# board.net
KiCad netlist of a schematic drawn in EAGLE
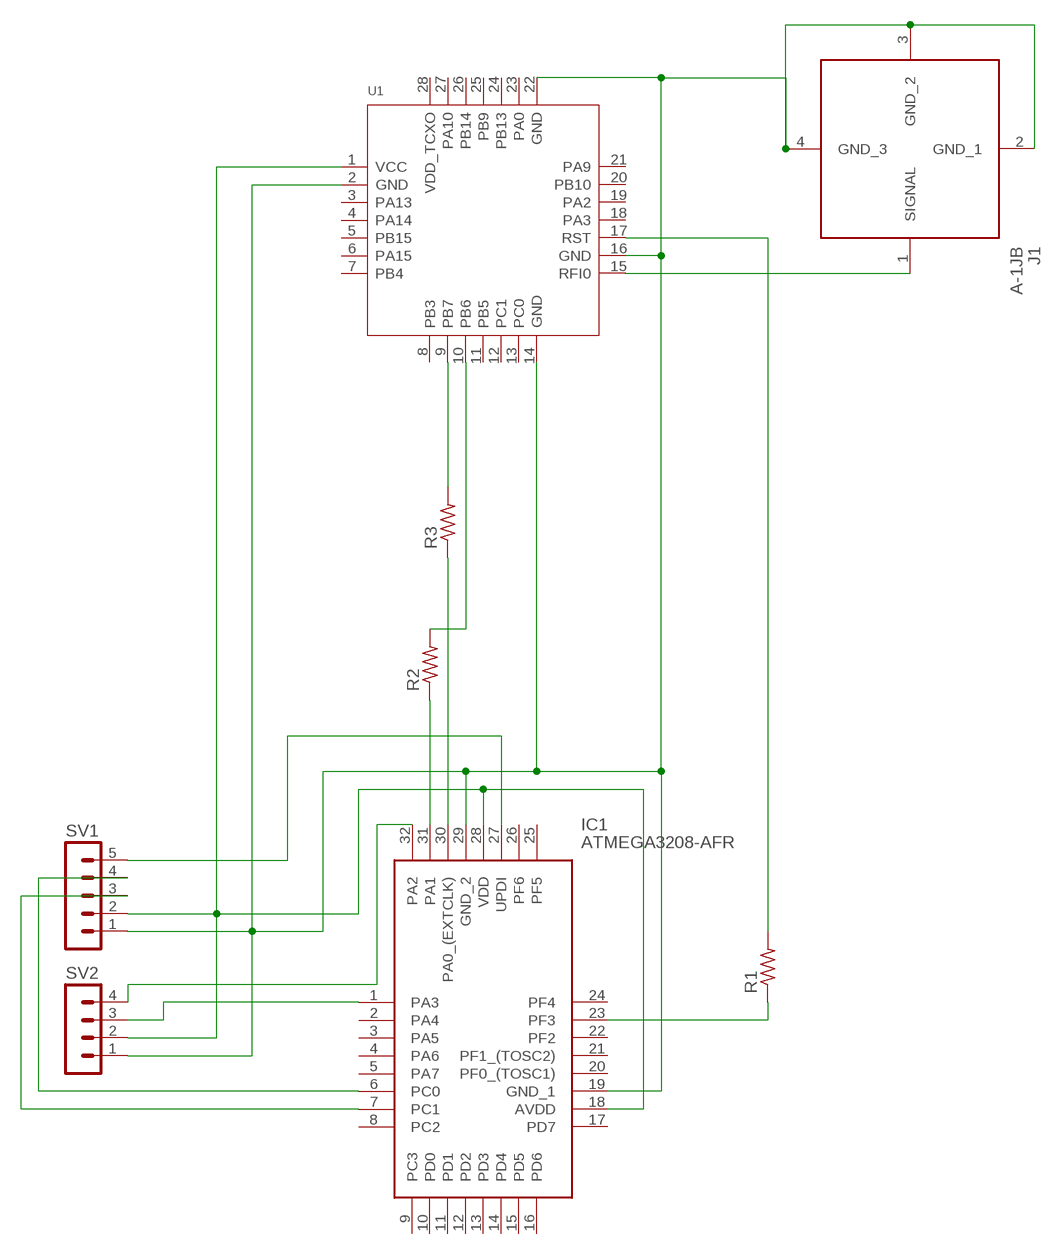
[diagram p0: schematic, sheet 1]

(export (version "E")
  (design (tool "Eeschema 10.0.6"))
  (components
    (comp (ref "IC1")
      (value "ATMEGA3208-AFR")
      (footprint "eagle-import:QFP80P900X900X120-32N")
      (fields (field (name "MOUSER_PART_NUMBER") "579-ATMEGA3208AFR"))
      (libsource (lib "eagle-import") (part "ATMEGA3208-AFR"))
    )
    (comp (ref "J1")
      (value "A-1JB")
      (footprint "eagle-import:A1JB")
      (fields (field (name "MOUSER_PART_NUMBER") "523-A-1JB"))
      (libsource (lib "eagle-import") (part "A-1JB"))
    )
    (comp (ref "R1")
      (value "22")
      (footprint "eagle-import:RES_0805")
      (fields
        (field (name "DIGIKEY_PART_NUMBER") "541-0.0ATR-ND")
        (field (name "MANUFACTURER") "Vishay Dale")
        (field (name "MPN") "CRCW08050000Z0EA")
        (field (name "CREATED_BY") "PCBLayout.com")
      )
      (libsource (lib "eagle-import") (part "CRCW08050000Z0EA"))
    )
    (comp (ref "R2")
      (value "22")
      (footprint "eagle-import:RES_0805")
      (fields
        (field (name "DIGIKEY_PART_NUMBER") "541-0.0ATR-ND")
        (field (name "MANUFACTURER") "Vishay Dale")
        (field (name "MPN") "CRCW08050000Z0EA")
        (field (name "CREATED_BY") "PCBLayout.com")
      )
      (libsource (lib "eagle-import") (part "CRCW08050000Z0EA"))
    )
    (comp (ref "R3")
      (value "22")
      (footprint "eagle-import:RES_0805")
      (fields
        (field (name "DIGIKEY_PART_NUMBER") "541-0.0ATR-ND")
        (field (name "MANUFACTURER") "Vishay Dale")
        (field (name "MPN") "CRCW08050000Z0EA")
        (field (name "CREATED_BY") "PCBLayout.com")
      )
      (libsource (lib "eagle-import") (part "CRCW08050000Z0EA"))
    )
    (comp (ref "SV1")
      (value "MA05-1")
      (footprint "eagle-import:MA05-1")
      (libsource (lib "eagle-import") (part "MA05-1"))
    )
    (comp (ref "SV2")
      (value "MA04-1")
      (footprint "eagle-import:MA04-1")
      (libsource (lib "eagle-import") (part "MA04-1"))
    )
    (comp (ref "U1")
      (value "MODULE_LORA_E5")
      (footprint "eagle-import:MODULE28P-1.25-12X12X2.5MM")
      (libsource (lib "eagle-import") (part "MODULE_LORA_E5"))
    )
  )
  (nets
    (net (code "1") (name "Net-(IC1-AVDD)") (class "Default")
      (node (ref "IC1") (pin "18") (pinfunction "AVDD_18") (pintype "bidirectional"))
      (node (ref "IC1") (pin "28") (pinfunction "VDD_28") (pintype "bidirectional"))
      (node (ref "SV1") (pin "2") (pinfunction "2_2") (pintype "passive"))
      (node (ref "SV2") (pin "2") (pinfunction "2_2") (pintype "passive"))
      (node (ref "U1") (pin "1") (pinfunction "VCC_1") (pintype "bidirectional"))
    )
    (net (code "2") (name "Net-(IC1-GND_1)") (class "Default")
      (node (ref "IC1") (pin "19") (pinfunction "GND_1_19") (pintype "bidirectional"))
      (node (ref "IC1") (pin "29") (pinfunction "GND_2_29") (pintype "bidirectional"))
      (node (ref "J1") (pin "2") (pinfunction "GND_1_2") (pintype "bidirectional"))
      (node (ref "J1") (pin "3") (pinfunction "GND_2_3") (pintype "bidirectional"))
      (node (ref "J1") (pin "4") (pinfunction "GND_3_4") (pintype "bidirectional"))
      (node (ref "SV1") (pin "1") (pinfunction "1_1") (pintype "passive"))
      (node (ref "SV2") (pin "1") (pinfunction "1_1") (pintype "passive"))
      (node (ref "U1") (pin "14") (pinfunction "GND_14") (pintype "bidirectional"))
      (node (ref "U1") (pin "16") (pinfunction "GND_16") (pintype "bidirectional"))
      (node (ref "U1") (pin "2") (pinfunction "GND_2") (pintype "bidirectional"))
      (node (ref "U1") (pin "22") (pinfunction "GND_22") (pintype "bidirectional"))
    )
    (net (code "3") (name "Net-(IC1-PA0_(EXTCLK))") (class "Default")
      (node (ref "IC1") (pin "30") (pinfunction "PA0_(EXTCLK)_30") (pintype "bidirectional"))
      (node (ref "R3") (pin "1") (pinfunction "1_1") (pintype "passive"))
    )
    (net (code "4") (name "Net-(IC1-PA1)") (class "Default")
      (node (ref "IC1") (pin "31") (pinfunction "PA1_31") (pintype "bidirectional"))
      (node (ref "R2") (pin "1") (pinfunction "1_1") (pintype "passive"))
    )
    (net (code "5") (name "Net-(IC1-PA2)") (class "Default")
      (node (ref "IC1") (pin "32") (pinfunction "PA2_32") (pintype "bidirectional"))
      (node (ref "SV2") (pin "4") (pinfunction "4_4") (pintype "passive"))
    )
    (net (code "6") (name "Net-(IC1-PA3)") (class "Default")
      (node (ref "IC1") (pin "1") (pinfunction "PA3_1") (pintype "bidirectional"))
      (node (ref "SV2") (pin "3") (pinfunction "3_3") (pintype "passive"))
    )
    (net (code "7") (name "Net-(IC1-PC0)") (class "Default")
      (node (ref "IC1") (pin "6") (pinfunction "PC0_6") (pintype "bidirectional"))
      (node (ref "SV1") (pin "4") (pinfunction "4_4") (pintype "passive"))
    )
    (net (code "8") (name "Net-(IC1-PC1)") (class "Default")
      (node (ref "IC1") (pin "7") (pinfunction "PC1_7") (pintype "bidirectional"))
      (node (ref "SV1") (pin "3") (pinfunction "3_3") (pintype "passive"))
    )
    (net (code "9") (name "Net-(IC1-PF3)") (class "Default")
      (node (ref "IC1") (pin "23") (pinfunction "PF3_23") (pintype "bidirectional"))
      (node (ref "R1") (pin "1") (pinfunction "1_1") (pintype "passive"))
    )
    (net (code "10") (name "Net-(IC1-UPDI)") (class "Default")
      (node (ref "IC1") (pin "27") (pinfunction "UPDI_27") (pintype "bidirectional"))
      (node (ref "SV1") (pin "5") (pinfunction "5_5") (pintype "passive"))
    )
    (net (code "11") (name "Net-(J1-SIGNAL)") (class "Default")
      (node (ref "J1") (pin "1") (pinfunction "SIGNAL_1") (pintype "bidirectional"))
      (node (ref "U1") (pin "15") (pinfunction "RFI0_15") (pintype "bidirectional"))
    )
    (net (code "12") (name "Net-(U1-PB6)") (class "Default")
      (node (ref "R2") (pin "2") (pinfunction "2_2") (pintype "passive"))
      (node (ref "U1") (pin "10") (pinfunction "PB6_10") (pintype "bidirectional"))
    )
    (net (code "13") (name "Net-(U1-PB7)") (class "Default")
      (node (ref "R3") (pin "2") (pinfunction "2_2") (pintype "passive"))
      (node (ref "U1") (pin "9") (pinfunction "PB7_9") (pintype "bidirectional"))
    )
    (net (code "14") (name "Net-(U1-RST)") (class "Default")
      (node (ref "R1") (pin "2") (pinfunction "2_2") (pintype "passive"))
      (node (ref "U1") (pin "17") (pinfunction "RST_17") (pintype "bidirectional"))
    )
    (net (code "15") (name "unconnected-(IC1-PA4-Pad2)") (class "Default")
      (node (ref "IC1") (pin "2") (pinfunction "PA4_2") (pintype "bidirectional"))
    )
    (net (code "16") (name "unconnected-(IC1-PA5-Pad3)") (class "Default")
      (node (ref "IC1") (pin "3") (pinfunction "PA5_3") (pintype "bidirectional"))
    )
    (net (code "17") (name "unconnected-(IC1-PA6-Pad4)") (class "Default")
      (node (ref "IC1") (pin "4") (pinfunction "PA6_4") (pintype "bidirectional"))
    )
    (net (code "18") (name "unconnected-(IC1-PA7-Pad5)") (class "Default")
      (node (ref "IC1") (pin "5") (pinfunction "PA7_5") (pintype "bidirectional"))
    )
    (net (code "19") (name "unconnected-(IC1-PC2-Pad8)") (class "Default")
      (node (ref "IC1") (pin "8") (pinfunction "PC2_8") (pintype "bidirectional"))
    )
    (net (code "20") (name "unconnected-(IC1-PC3-Pad9)") (class "Default")
      (node (ref "IC1") (pin "9") (pinfunction "PC3_9") (pintype "bidirectional"))
    )
    (net (code "21") (name "unconnected-(IC1-PD0-Pad10)") (class "Default")
      (node (ref "IC1") (pin "10") (pinfunction "PD0_10") (pintype "bidirectional"))
    )
    (net (code "22") (name "unconnected-(IC1-PD1-Pad11)") (class "Default")
      (node (ref "IC1") (pin "11") (pinfunction "PD1_11") (pintype "bidirectional"))
    )
    (net (code "23") (name "unconnected-(IC1-PD2-Pad12)") (class "Default")
      (node (ref "IC1") (pin "12") (pinfunction "PD2_12") (pintype "bidirectional"))
    )
    (net (code "24") (name "unconnected-(IC1-PD3-Pad13)") (class "Default")
      (node (ref "IC1") (pin "13") (pinfunction "PD3_13") (pintype "bidirectional"))
    )
    (net (code "25") (name "unconnected-(IC1-PD4-Pad14)") (class "Default")
      (node (ref "IC1") (pin "14") (pinfunction "PD4_14") (pintype "bidirectional"))
    )
    (net (code "26") (name "unconnected-(IC1-PD5-Pad15)") (class "Default")
      (node (ref "IC1") (pin "15") (pinfunction "PD5_15") (pintype "bidirectional"))
    )
    (net (code "27") (name "unconnected-(IC1-PD6-Pad16)") (class "Default")
      (node (ref "IC1") (pin "16") (pinfunction "PD6_16") (pintype "bidirectional"))
    )
    (net (code "28") (name "unconnected-(IC1-PD7-Pad17)") (class "Default")
      (node (ref "IC1") (pin "17") (pinfunction "PD7_17") (pintype "bidirectional"))
    )
    (net (code "29") (name "unconnected-(IC1-PF0_(TOSC1)-Pad20)") (class "Default")
      (node (ref "IC1") (pin "20") (pinfunction "PF0_(TOSC1)_20") (pintype "bidirectional"))
    )
    (net (code "30") (name "unconnected-(IC1-PF1_(TOSC2)-Pad21)") (class "Default")
      (node (ref "IC1") (pin "21") (pinfunction "PF1_(TOSC2)_21") (pintype "bidirectional"))
    )
    (net (code "31") (name "unconnected-(IC1-PF2-Pad22)") (class "Default")
      (node (ref "IC1") (pin "22") (pinfunction "PF2_22") (pintype "bidirectional"))
    )
    (net (code "32") (name "unconnected-(IC1-PF4-Pad24)") (class "Default")
      (node (ref "IC1") (pin "24") (pinfunction "PF4_24") (pintype "bidirectional"))
    )
    (net (code "33") (name "unconnected-(IC1-PF5-Pad25)") (class "Default")
      (node (ref "IC1") (pin "25") (pinfunction "PF5_25") (pintype "bidirectional"))
    )
    (net (code "34") (name "unconnected-(IC1-PF6-Pad26)") (class "Default")
      (node (ref "IC1") (pin "26") (pinfunction "PF6_26") (pintype "bidirectional"))
    )
    (net (code "35") (name "unconnected-(U1-PA0-Pad23)") (class "Default")
      (node (ref "U1") (pin "23") (pinfunction "PA0_23") (pintype "bidirectional"))
    )
    (net (code "36") (name "unconnected-(U1-PA2-Pad19)") (class "Default")
      (node (ref "U1") (pin "19") (pinfunction "PA2_19") (pintype "bidirectional"))
    )
    (net (code "37") (name "unconnected-(U1-PA3-Pad18)") (class "Default")
      (node (ref "U1") (pin "18") (pinfunction "PA3_18") (pintype "bidirectional"))
    )
    (net (code "38") (name "unconnected-(U1-PA9-Pad21)") (class "Default")
      (node (ref "U1") (pin "21") (pinfunction "PA9_21") (pintype "bidirectional"))
    )
    (net (code "39") (name "unconnected-(U1-PA10-Pad27)") (class "Default")
      (node (ref "U1") (pin "27") (pinfunction "PA10_27") (pintype "bidirectional"))
    )
    (net (code "40") (name "unconnected-(U1-PA13-Pad3)") (class "Default")
      (node (ref "U1") (pin "3") (pinfunction "PA13_3") (pintype "bidirectional"))
    )
    (net (code "41") (name "unconnected-(U1-PA14-Pad4)") (class "Default")
      (node (ref "U1") (pin "4") (pinfunction "PA14_4") (pintype "bidirectional"))
    )
    (net (code "42") (name "unconnected-(U1-PA15-Pad6)") (class "Default")
      (node (ref "U1") (pin "6") (pinfunction "PA15_6") (pintype "bidirectional"))
    )
    (net (code "43") (name "unconnected-(U1-PB3-Pad8)") (class "Default")
      (node (ref "U1") (pin "8") (pinfunction "PB3_8") (pintype "bidirectional"))
    )
    (net (code "44") (name "unconnected-(U1-PB4-Pad7)") (class "Default")
      (node (ref "U1") (pin "7") (pinfunction "PB4_7") (pintype "bidirectional"))
    )
    (net (code "45") (name "unconnected-(U1-PB5-Pad11)") (class "Default")
      (node (ref "U1") (pin "11") (pinfunction "PB5_11") (pintype "bidirectional"))
    )
    (net (code "46") (name "unconnected-(U1-PB9-Pad25)") (class "Default")
      (node (ref "U1") (pin "25") (pinfunction "PB9_25") (pintype "bidirectional"))
    )
    (net (code "47") (name "unconnected-(U1-PB10-Pad20)") (class "Default")
      (node (ref "U1") (pin "20") (pinfunction "PB10_20") (pintype "bidirectional"))
    )
    (net (code "48") (name "unconnected-(U1-PB13-Pad24)") (class "Default")
      (node (ref "U1") (pin "24") (pinfunction "PB13_24") (pintype "bidirectional"))
    )
    (net (code "49") (name "unconnected-(U1-PB14-Pad26)") (class "Default")
      (node (ref "U1") (pin "26") (pinfunction "PB14_26") (pintype "bidirectional"))
    )
    (net (code "50") (name "unconnected-(U1-PB15-Pad5)") (class "Default")
      (node (ref "U1") (pin "5") (pinfunction "PB15_5") (pintype "bidirectional"))
    )
    (net (code "51") (name "unconnected-(U1-PC0-Pad13)") (class "Default")
      (node (ref "U1") (pin "13") (pinfunction "PC0_13") (pintype "bidirectional"))
    )
    (net (code "52") (name "unconnected-(U1-PC1-Pad12)") (class "Default")
      (node (ref "U1") (pin "12") (pinfunction "PC1_12") (pintype "bidirectional"))
    )
    (net (code "53") (name "unconnected-(U1-VDD_TCXO-Pad28)") (class "Default")
      (node (ref "U1") (pin "28") (pinfunction "VDD_TCXO_28") (pintype "bidirectional"))
    )
  )
)
